# Adafruit_MSA311.net
KiCad netlist of a schematic drawn in EAGLE
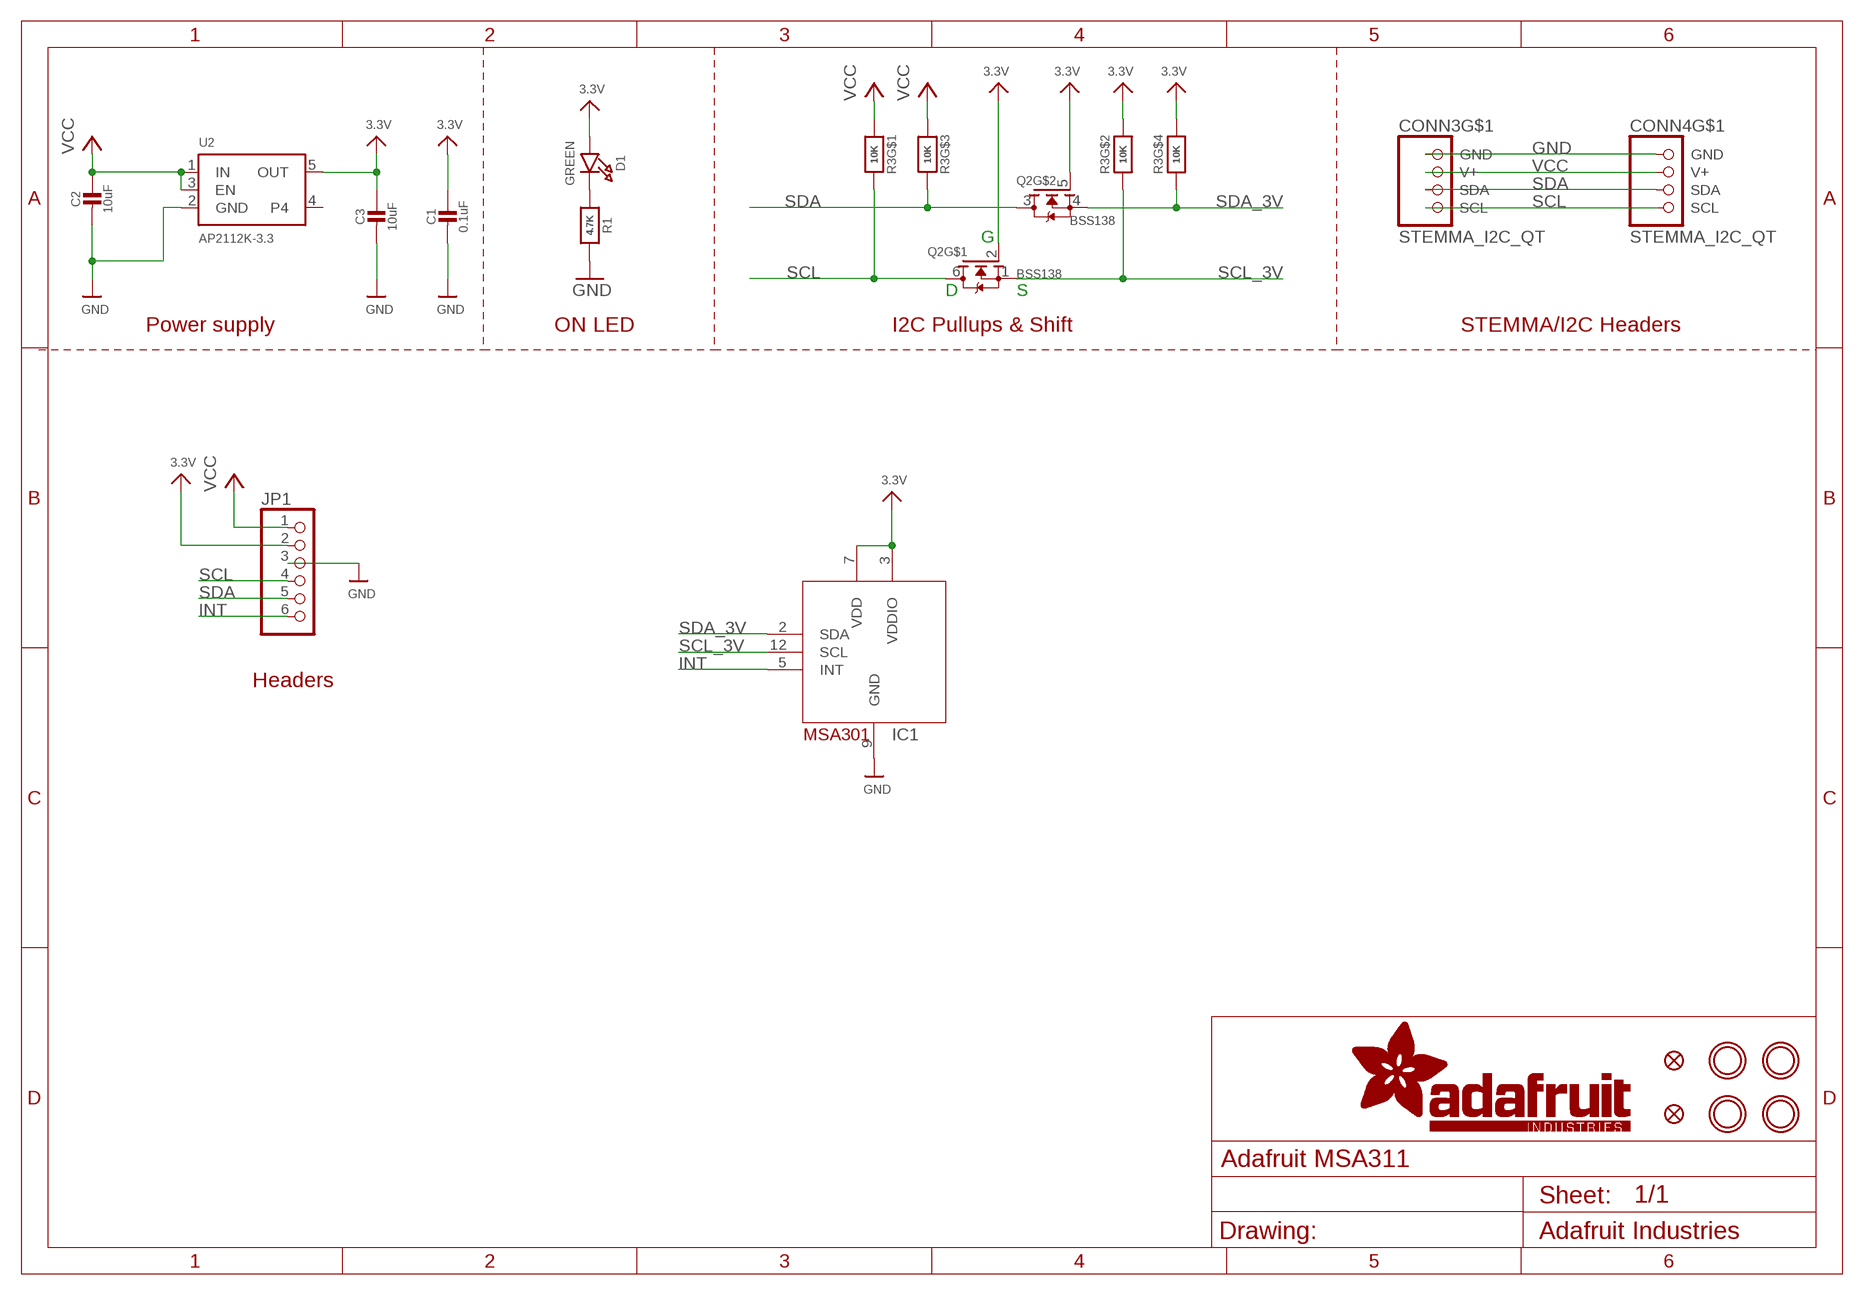
[diagram p0: schematic, sheet 1]

(export (version "E")
  (design (tool "Eeschema 10.0.6"))
  (components
    (comp (ref "C1")
      (value "0.1uF")
      (footprint "eagle-import:0603-NO")
      (libsource (lib "eagle-import") (part "CAP_CERAMIC0603_NO"))
    )
    (comp (ref "C2")
      (value "10uF")
      (footprint "eagle-import:0805-NO")
      (libsource (lib "eagle-import") (part "CAP_CERAMIC0805-NOOUTLINE"))
    )
    (comp (ref "C3")
      (value "10uF")
      (footprint "eagle-import:0805-NO")
      (libsource (lib "eagle-import") (part "CAP_CERAMIC0805-NOOUTLINE"))
    )
    (comp (ref "CONN3")
      (value "STEMMA_I2C_QT")
      (footprint "eagle-import:JST_SH4")
      (libsource (lib "eagle-import") (part "STEMMA_I2C_QT"))
    )
    (comp (ref "CONN4")
      (value "STEMMA_I2C_QT")
      (footprint "eagle-import:JST_SH4")
      (libsource (lib "eagle-import") (part "STEMMA_I2C_QT"))
    )
    (comp (ref "D1")
      (value "GREEN")
      (footprint "eagle-import:CHIPLED_0603_NOOUTLINE")
      (libsource (lib "eagle-import") (part "LED0603_NOOUTLINE"))
    )
    (comp (ref "FID3")
      (value "FIDUCIAL_1MM")
      (footprint "eagle-import:FIDUCIAL_1MM")
      (libsource (lib "eagle-import") (part "FIDUCIAL_1MM"))
    )
    (comp (ref "FID4")
      (value "FIDUCIAL_1MM")
      (footprint "eagle-import:FIDUCIAL_1MM")
      (libsource (lib "eagle-import") (part "FIDUCIAL_1MM"))
    )
    (comp (ref "IC1")
      (value "MSA301")
      (footprint "eagle-import:LGA12_2X2MM")
      (libsource (lib "eagle-import") (part "MSA301"))
    )
    (comp (ref "JP1")
      (value "HEADER-1X670MIL")
      (footprint "eagle-import:1X06_ROUND_70")
      (libsource (lib "eagle-import") (part "HEADER-1X670MIL"))
    )
    (comp (ref "Q2")
      (value "BSS138")
      (footprint "eagle-import:SOT363")
      (libsource (lib "eagle-import") (part "MOSFET-N_DUAL"))
    )
    (comp (ref "R1")
      (value "4.7K")
      (footprint "eagle-import:0603-NO")
      (libsource (lib "eagle-import") (part "RESISTOR_0603_NOOUT"))
    )
    (comp (ref "R3")
      (value "10K")
      (footprint "eagle-import:RESPACK_4X0603")
      (libsource (lib "eagle-import") (part "RESISTOR_4PACK"))
    )
    (comp (ref "U$1")
      (value "MOUNTINGHOLE2.5")
      (footprint "eagle-import:MOUNTINGHOLE_2.5_PLATED")
      (libsource (lib "eagle-import") (part "MOUNTINGHOLE2.5"))
    )
    (comp (ref "U$17")
      (value "MOUNTINGHOLE2.5")
      (footprint "eagle-import:MOUNTINGHOLE_2.5_PLATED")
      (libsource (lib "eagle-import") (part "MOUNTINGHOLE2.5"))
    )
    (comp (ref "U$19")
      (value "MOUNTINGHOLE2.5")
      (footprint "eagle-import:MOUNTINGHOLE_2.5_PLATED")
      (libsource (lib "eagle-import") (part "MOUNTINGHOLE2.5"))
    )
    (comp (ref "U$21")
      (value "MOUNTINGHOLE2.5")
      (footprint "eagle-import:MOUNTINGHOLE_2.5_PLATED")
      (libsource (lib "eagle-import") (part "MOUNTINGHOLE2.5"))
    )
    (comp (ref "U2")
      (value "AP2112K-3.3")
      (footprint "eagle-import:SOT23-5")
      (libsource (lib "eagle-import") (part "VREG_SOT23-5"))
    )
  )
  (nets
    (net (code "1") (name "/INT") (class "Default")
      (node (ref "IC1") (pin "5") (pinfunction "INT_5") (pintype "output"))
      (node (ref "JP1") (pin "6") (pinfunction "6_6") (pintype "passive"))
    )
    (net (code "2") (name "/SCL") (class "Default")
      (node (ref "CONN3") (pin "4") (pinfunction "SCL_4") (pintype "passive"))
      (node (ref "CONN4") (pin "4") (pinfunction "SCL_4") (pintype "passive"))
      (node (ref "JP1") (pin "4") (pinfunction "4_4") (pintype "passive"))
      (node (ref "Q2") (pin "6") (pinfunction "D_6") (pintype "bidirectional"))
      (node (ref "R3") (pin "8") (pinfunction "2_8") (pintype "passive"))
    )
    (net (code "3") (name "/SCL_3V") (class "Default")
      (node (ref "IC1") (pin "12") (pinfunction "SCL_12") (pintype "bidirectional"))
      (node (ref "Q2") (pin "1") (pinfunction "S_1") (pintype "bidirectional"))
      (node (ref "R3") (pin "7") (pinfunction "2_7") (pintype "passive"))
    )
    (net (code "4") (name "/SDA") (class "Default")
      (node (ref "CONN3") (pin "3") (pinfunction "SDA_3") (pintype "passive"))
      (node (ref "CONN4") (pin "3") (pinfunction "SDA_3") (pintype "passive"))
      (node (ref "JP1") (pin "5") (pinfunction "5_5") (pintype "passive"))
      (node (ref "Q2") (pin "3") (pinfunction "D_3") (pintype "bidirectional"))
      (node (ref "R3") (pin "6") (pinfunction "2_6") (pintype "passive"))
    )
    (net (code "5") (name "/SDA_3V") (class "Default")
      (node (ref "IC1") (pin "2") (pinfunction "SDA_2") (pintype "bidirectional"))
      (node (ref "Q2") (pin "4") (pinfunction "S_4") (pintype "bidirectional"))
      (node (ref "R3") (pin "5") (pinfunction "2_5") (pintype "passive"))
    )
    (net (code "6") (name "3.3V") (class "Default")
      (node (ref "C1") (pin "1") (pinfunction "1_1") (pintype "passive"))
      (node (ref "C3") (pin "1") (pinfunction "1_1") (pintype "passive"))
      (node (ref "D1") (pin "A") (pinfunction "A_A") (pintype "passive"))
      (node (ref "IC1") (pin "3") (pinfunction "VDDIO_3") (pintype "power_in"))
      (node (ref "IC1") (pin "7") (pinfunction "VDD_7") (pintype "power_in"))
      (node (ref "JP1") (pin "2") (pinfunction "2_2") (pintype "passive"))
      (node (ref "Q2") (pin "2") (pinfunction "G_2") (pintype "bidirectional"))
      (node (ref "Q2") (pin "5") (pinfunction "G_5") (pintype "bidirectional"))
      (node (ref "R3") (pin "2") (pinfunction "1_2") (pintype "passive"))
      (node (ref "R3") (pin "4") (pinfunction "1_4") (pintype "passive"))
      (node (ref "U2") (pin "5") (pinfunction "OUT_5") (pintype "power_in"))
    )
    (net (code "7") (name "GND") (class "Default")
      (node (ref "C1") (pin "2") (pinfunction "2_2") (pintype "passive"))
      (node (ref "C2") (pin "2") (pinfunction "2_2") (pintype "passive"))
      (node (ref "C3") (pin "2") (pinfunction "2_2") (pintype "passive"))
      (node (ref "CONN3") (pin "1") (pinfunction "GND_1") (pintype "passive"))
      (node (ref "CONN4") (pin "1") (pinfunction "GND_1") (pintype "passive"))
      (node (ref "IC1") (pin "9") (pinfunction "GND_9") (pintype "power_in"))
      (node (ref "JP1") (pin "3") (pinfunction "3_3") (pintype "passive"))
      (node (ref "R1") (pin "2") (pinfunction "2_2") (pintype "passive"))
      (node (ref "U2") (pin "2") (pinfunction "GND_2") (pintype "power_in"))
    )
    (net (code "8") (name "Net-(D1-PadC)") (class "Default")
      (node (ref "D1") (pin "C") (pinfunction "C_C") (pintype "passive"))
      (node (ref "R1") (pin "1") (pinfunction "1_1") (pintype "passive"))
    )
    (net (code "9") (name "VCC") (class "Default")
      (node (ref "C2") (pin "1") (pinfunction "1_1") (pintype "passive"))
      (node (ref "CONN3") (pin "2") (pinfunction "V+_2") (pintype "passive"))
      (node (ref "CONN4") (pin "2") (pinfunction "V+_2") (pintype "passive"))
      (node (ref "JP1") (pin "1") (pinfunction "1_1") (pintype "passive"))
      (node (ref "R3") (pin "1") (pinfunction "1_1") (pintype "passive"))
      (node (ref "R3") (pin "3") (pinfunction "1_3") (pintype "passive"))
      (node (ref "U2") (pin "1") (pinfunction "IN_1") (pintype "power_in"))
      (node (ref "U2") (pin "3") (pinfunction "EN_3") (pintype "input"))
    )
    (net (code "10") (name "unconnected-(U2-P4-Pad4)") (class "Default")
      (node (ref "U2") (pin "4") (pinfunction "P4_4") (pintype "bidirectional"))
    )
  )
)
